# arduino-isp.net
KiCad netlist of a schematic drawn in EAGLE
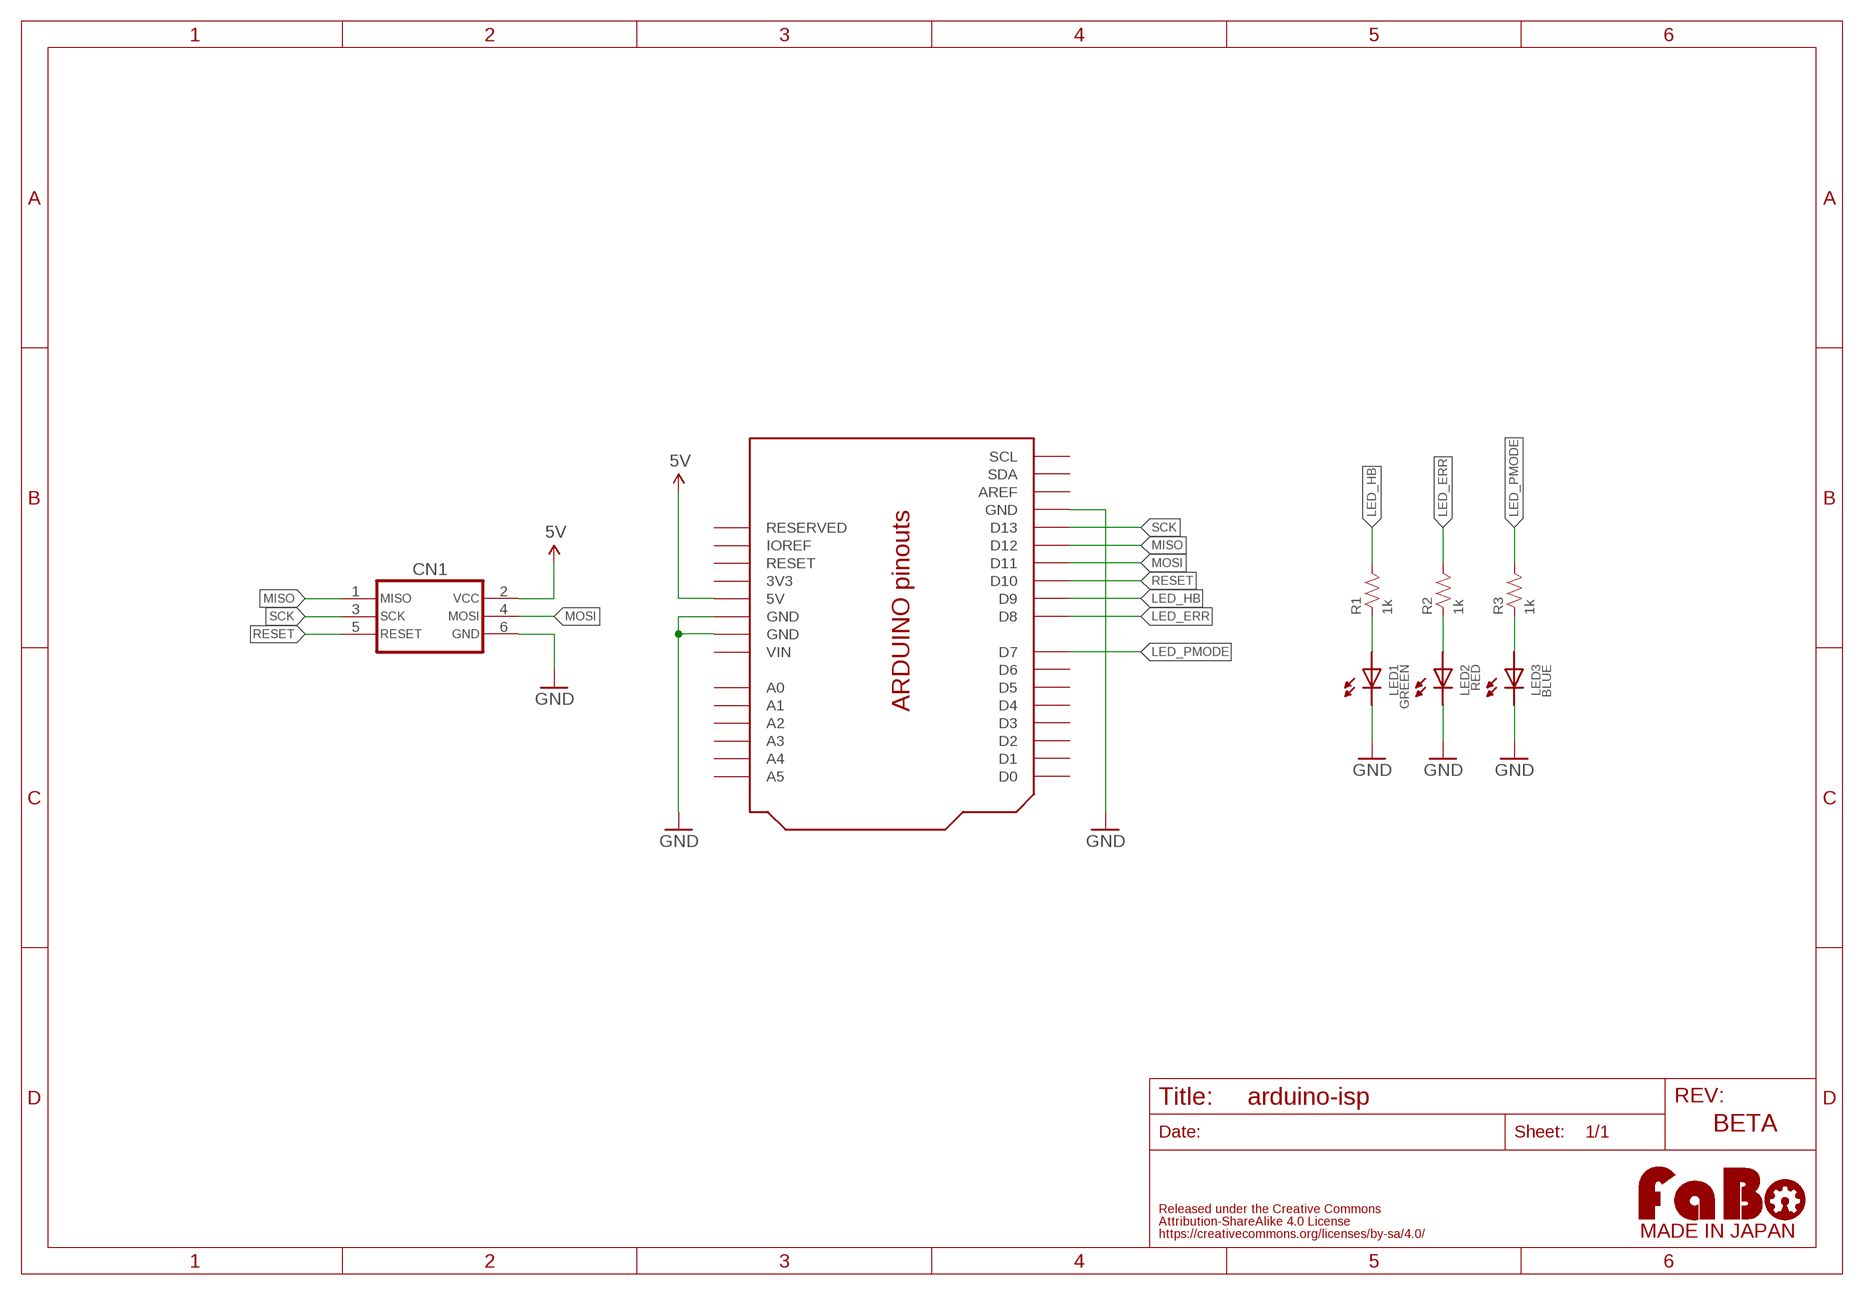
[diagram p0: schematic, sheet 1]

(export (version "E")
  (design (tool "Eeschema 10.0.6"))
  (components
    (comp (ref "CN1")
      (value "AVR_ISP_BOX")
      (footprint "eagle-import:BOX_2X3")
      (libsource (lib "eagle-import") (part "AVR_ISP_BOX"))
    )
    (comp (ref "LED1")
      (value "GREEN")
      (footprint "eagle-import:LED_5MM")
      (libsource (lib "eagle-import") (part "LED-5MM"))
    )
    (comp (ref "LED2")
      (value "RED")
      (footprint "eagle-import:LED_5MM")
      (libsource (lib "eagle-import") (part "LED-5MM"))
    )
    (comp (ref "LED3")
      (value "BLUE")
      (footprint "eagle-import:LED_5MM")
      (libsource (lib "eagle-import") (part "LED-5MM"))
    )
    (comp (ref "R1")
      (value "1k")
      (footprint "eagle-import:AXL-REGULAR")
      (libsource (lib "eagle-import") (part "RESISTOR-AXL-REGULAR"))
    )
    (comp (ref "R2")
      (value "1k")
      (footprint "eagle-import:AXL-REGULAR")
      (libsource (lib "eagle-import") (part "RESISTOR-AXL-REGULAR"))
    )
    (comp (ref "R3")
      (value "1k")
      (footprint "eagle-import:AXL-REGULAR")
      (libsource (lib "eagle-import") (part "RESISTOR-AXL-REGULAR"))
    )
    (comp (ref "U$2")
      (value "LOGO_FABO-M")
      (footprint "eagle-import:LOGO_FABO_MS")
      (libsource (lib "eagle-import") (part "LOGO_FABO-M"))
    )
    (comp (ref "U1")
      (value "ARDUINO_UNO_R3_SHIELD-HALF")
      (footprint "eagle-import:ARDUINO_SHIELD_HALF")
      (libsource (lib "eagle-import") (part "ARDUINO_UNO_R3_SHIELD-HALF"))
    )
  )
  (nets
    (net (code "1") (name "/3V3") (class "Default")
      (node (ref "U1") (pin "3V3") (pinfunction "3V3_3V3") (pintype "power_in"))
    )
    (net (code "2") (name "/VIN") (class "Default")
      (node (ref "U1") (pin "VIN") (pinfunction "VIN_VIN") (pintype "power_in"))
    )
    (net (code "3") (name "5V") (class "Default")
      (node (ref "CN1") (pin "2") (pinfunction "2_2") (pintype "passive"))
      (node (ref "U1") (pin "5V") (pinfunction "5V_5V") (pintype "power_in"))
    )
    (net (code "4") (name "GND") (class "Default")
      (node (ref "CN1") (pin "6") (pinfunction "6_6") (pintype "passive"))
      (node (ref "LED1") (pin "K") (pinfunction "CATHODE_K") (pintype "passive"))
      (node (ref "LED2") (pin "K") (pinfunction "CATHODE_K") (pintype "passive"))
      (node (ref "LED3") (pin "K") (pinfunction "CATHODE_K") (pintype "passive"))
      (node (ref "U1") (pin "GND1") (pinfunction "GND_GND1") (pintype "power_in"))
      (node (ref "U1") (pin "GND2") (pinfunction "GND_GND2") (pintype "power_in"))
      (node (ref "U1") (pin "GND3") (pinfunction "GND_GND3") (pintype "power_in"))
    )
    (net (code "5") (name "LED_ERR") (class "Default")
      (node (ref "R2") (pin "2") (pinfunction "2_2") (pintype "bidirectional"))
      (node (ref "U1") (pin "D8") (pinfunction "D8_D8") (pintype "bidirectional"))
    )
    (net (code "6") (name "LED_HB") (class "Default")
      (node (ref "R1") (pin "2") (pinfunction "2_2") (pintype "bidirectional"))
      (node (ref "U1") (pin "D9") (pinfunction "D9_D9") (pintype "bidirectional"))
    )
    (net (code "7") (name "LED_PMODE") (class "Default")
      (node (ref "R3") (pin "2") (pinfunction "2_2") (pintype "bidirectional"))
      (node (ref "U1") (pin "D7") (pinfunction "D7_D7") (pintype "bidirectional"))
    )
    (net (code "8") (name "MISO") (class "Default")
      (node (ref "CN1") (pin "1") (pinfunction "1_1") (pintype "passive"))
      (node (ref "U1") (pin "D12") (pinfunction "D12_D12") (pintype "bidirectional"))
    )
    (net (code "9") (name "MOSI") (class "Default")
      (node (ref "CN1") (pin "4") (pinfunction "4_4") (pintype "passive"))
      (node (ref "U1") (pin "D11") (pinfunction "D11_D11") (pintype "bidirectional"))
    )
    (net (code "10") (name "Net-(LED1-ANODE)") (class "Default")
      (node (ref "LED1") (pin "A") (pinfunction "ANODE_A") (pintype "passive"))
      (node (ref "R1") (pin "1") (pinfunction "1_1") (pintype "bidirectional"))
    )
    (net (code "11") (name "Net-(LED2-ANODE)") (class "Default")
      (node (ref "LED2") (pin "A") (pinfunction "ANODE_A") (pintype "passive"))
      (node (ref "R2") (pin "1") (pinfunction "1_1") (pintype "bidirectional"))
    )
    (net (code "12") (name "Net-(LED3-ANODE)") (class "Default")
      (node (ref "LED3") (pin "A") (pinfunction "ANODE_A") (pintype "passive"))
      (node (ref "R3") (pin "1") (pinfunction "1_1") (pintype "bidirectional"))
    )
    (net (code "13") (name "RESET") (class "Default")
      (node (ref "CN1") (pin "5") (pinfunction "5_5") (pintype "passive"))
      (node (ref "U1") (pin "D10") (pinfunction "D10_D10") (pintype "bidirectional"))
    )
    (net (code "14") (name "SCK") (class "Default")
      (node (ref "CN1") (pin "3") (pinfunction "3_3") (pintype "passive"))
      (node (ref "U1") (pin "D13") (pinfunction "D13_D13") (pintype "bidirectional"))
    )
    (net (code "15") (name "unconnected-(U1-PadA0)") (class "Default")
      (node (ref "U1") (pin "A0") (pinfunction "A0_A0") (pintype "bidirectional"))
    )
    (net (code "16") (name "unconnected-(U1-PadA1)") (class "Default")
      (node (ref "U1") (pin "A1") (pinfunction "A1_A1") (pintype "bidirectional"))
    )
    (net (code "17") (name "unconnected-(U1-PadA2)") (class "Default")
      (node (ref "U1") (pin "A2") (pinfunction "A2_A2") (pintype "bidirectional"))
    )
    (net (code "18") (name "unconnected-(U1-PadA3)") (class "Default")
      (node (ref "U1") (pin "A3") (pinfunction "A3_A3") (pintype "bidirectional"))
    )
    (net (code "19") (name "unconnected-(U1-PadA4)") (class "Default")
      (node (ref "U1") (pin "A4") (pinfunction "A4_A4") (pintype "bidirectional"))
    )
    (net (code "20") (name "unconnected-(U1-PadA5)") (class "Default")
      (node (ref "U1") (pin "A5") (pinfunction "A5_A5") (pintype "bidirectional"))
    )
    (net (code "21") (name "unconnected-(U1-PadAREF)") (class "Default")
      (node (ref "U1") (pin "AREF") (pinfunction "AREF_AREF") (pintype "bidirectional"))
    )
    (net (code "22") (name "unconnected-(U1-PadD0)") (class "Default")
      (node (ref "U1") (pin "D0") (pinfunction "D0_D0") (pintype "bidirectional"))
    )
    (net (code "23") (name "unconnected-(U1-PadD1)") (class "Default")
      (node (ref "U1") (pin "D1") (pinfunction "D1_D1") (pintype "bidirectional"))
    )
    (net (code "24") (name "unconnected-(U1-PadD2)") (class "Default")
      (node (ref "U1") (pin "D2") (pinfunction "D2_D2") (pintype "bidirectional"))
    )
    (net (code "25") (name "unconnected-(U1-PadD3)") (class "Default")
      (node (ref "U1") (pin "D3") (pinfunction "D3_D3") (pintype "bidirectional"))
    )
    (net (code "26") (name "unconnected-(U1-PadD4)") (class "Default")
      (node (ref "U1") (pin "D4") (pinfunction "D4_D4") (pintype "bidirectional"))
    )
    (net (code "27") (name "unconnected-(U1-PadD5)") (class "Default")
      (node (ref "U1") (pin "D5") (pinfunction "D5_D5") (pintype "bidirectional"))
    )
    (net (code "28") (name "unconnected-(U1-PadD6)") (class "Default")
      (node (ref "U1") (pin "D6") (pinfunction "D6_D6") (pintype "bidirectional"))
    )
    (net (code "29") (name "unconnected-(U1-PadIOREF)") (class "Default")
      (node (ref "U1") (pin "IOREF") (pinfunction "IOREF_IOREF") (pintype "output"))
    )
    (net (code "30") (name "unconnected-(U1-PadRESERVED)") (class "Default")
      (node (ref "U1") (pin "RESERVED") (pinfunction "RESERVED_RESERVED") (pintype "no_connect"))
    )
    (net (code "31") (name "unconnected-(U1-PadRESET)") (class "Default")
      (node (ref "U1") (pin "RESET") (pinfunction "RESET_RESET") (pintype "bidirectional"))
    )
    (net (code "32") (name "unconnected-(U1-PadSCL)") (class "Default")
      (node (ref "U1") (pin "SCL") (pinfunction "SCL_SCL") (pintype "bidirectional"))
    )
    (net (code "33") (name "unconnected-(U1-PadSDA)") (class "Default")
      (node (ref "U1") (pin "SDA") (pinfunction "SDA_SDA") (pintype "bidirectional"))
    )
  )
)
